# f103ret6_w25q64_20200910.net
KiCad netlist of a schematic drawn in Altium Designer
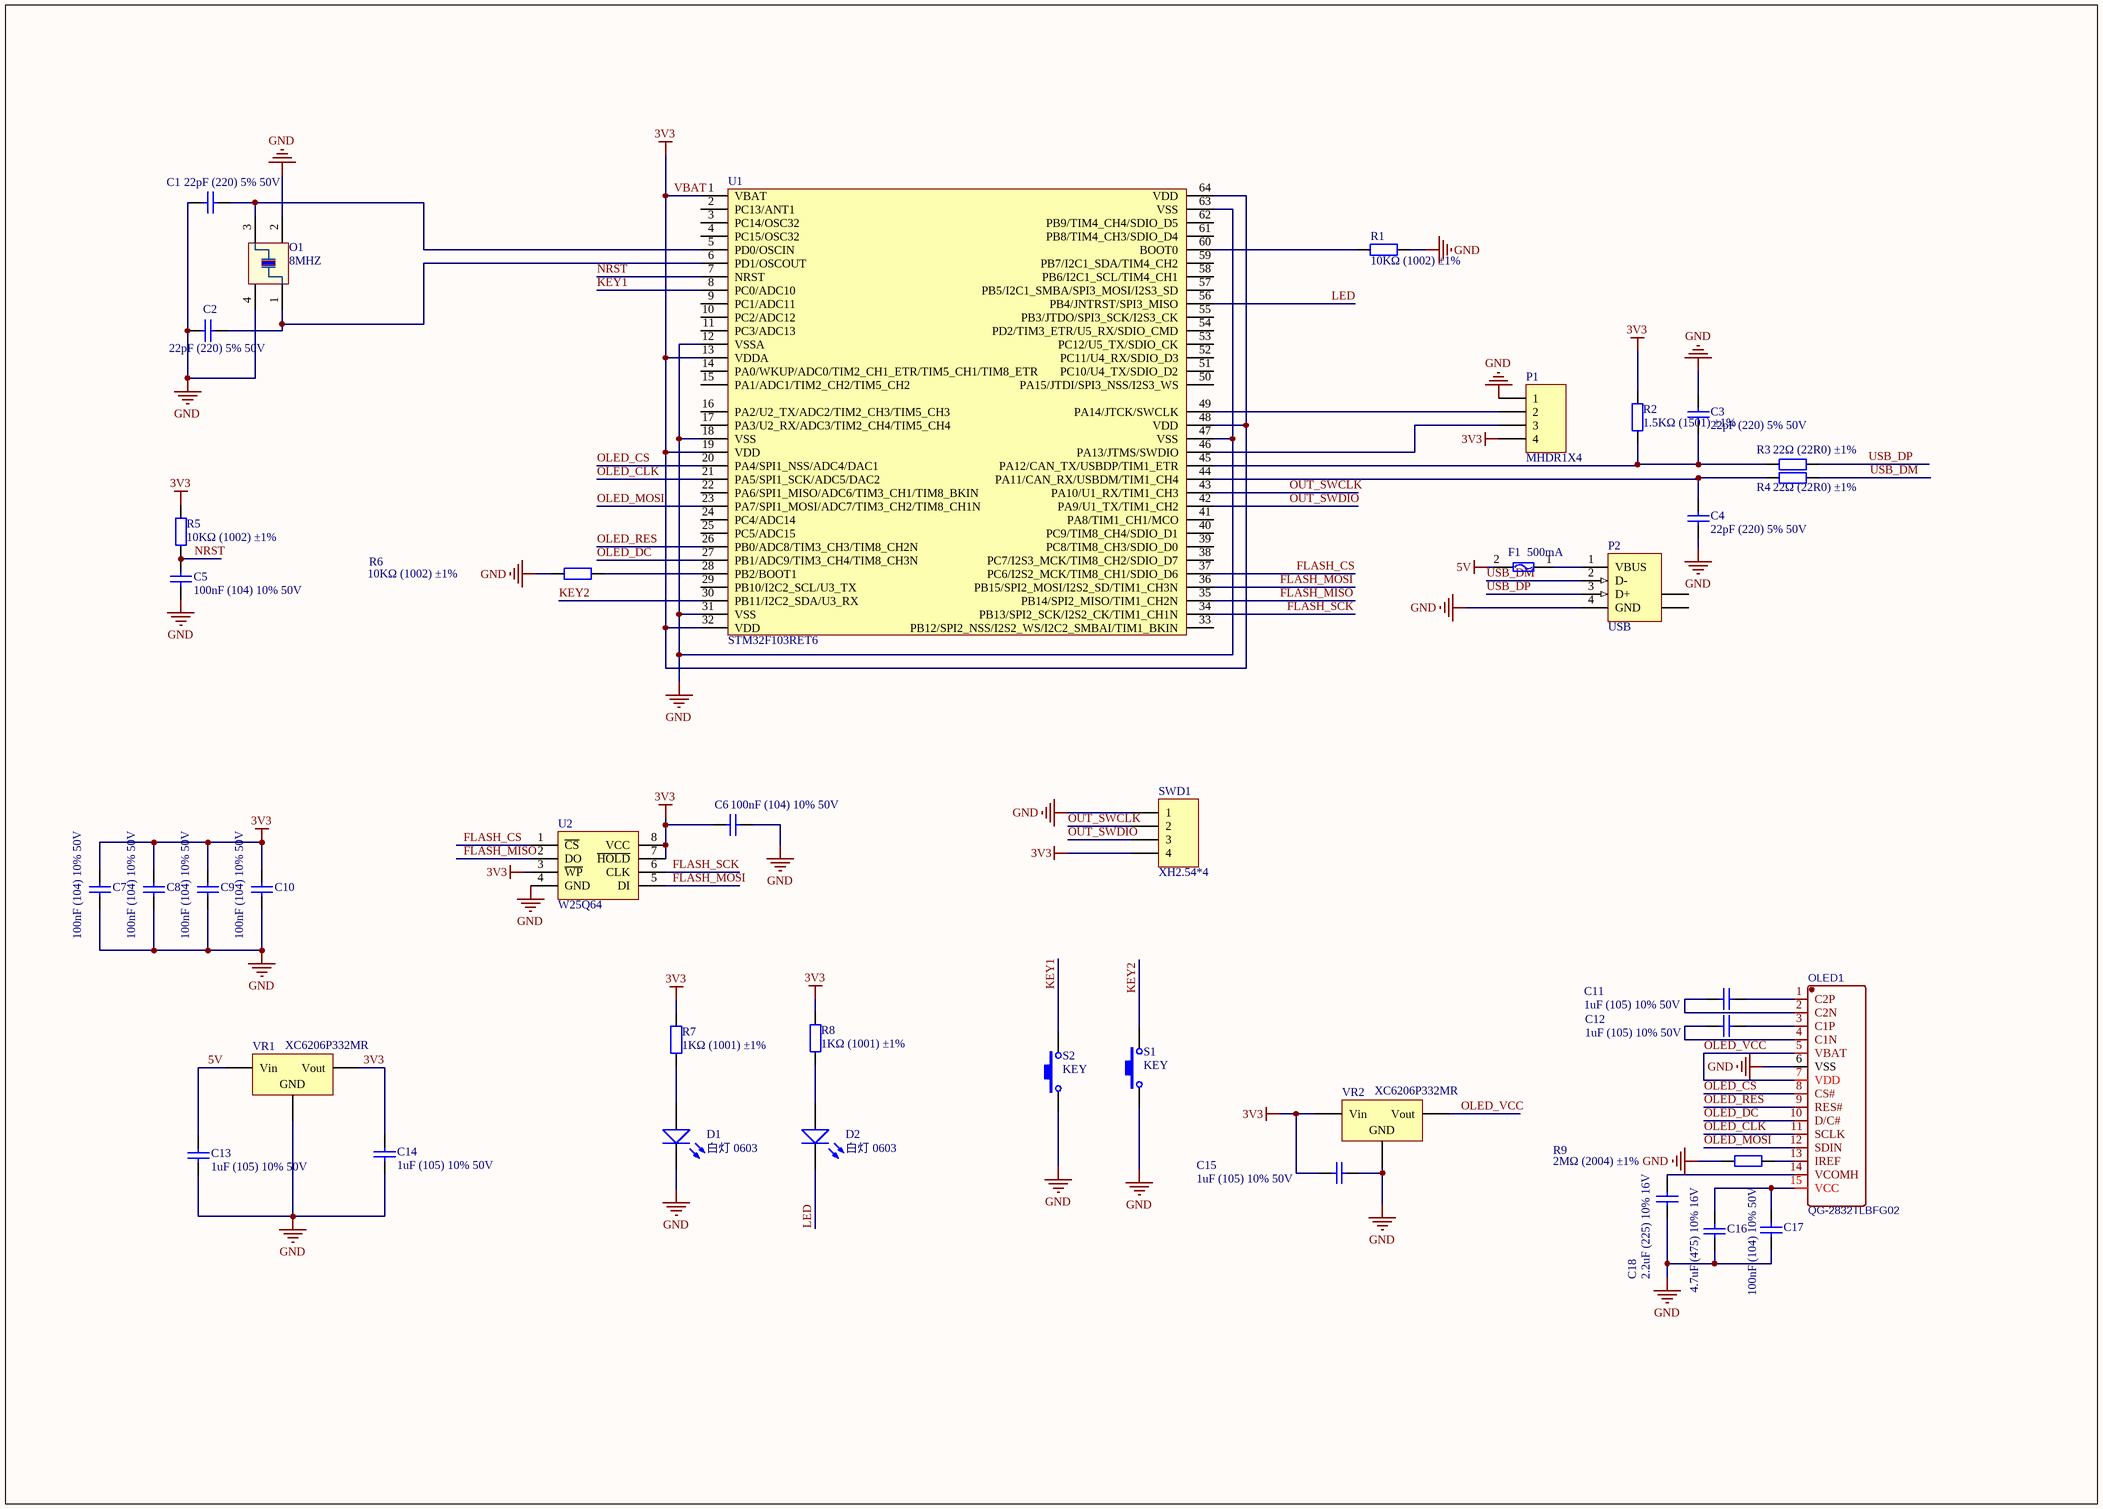
[diagram p0: f103ret6_w25q64_20200910.SchDoc]

(export (version "E")
  (design (tool "Eeschema 10.0.6"))
  (components
    (comp (ref "C1")
      (value "22pF (220) 5% 50V")
      (footprint "0603_C")
      (description "贴片电容")
      (libsource (lib "Miscellaneous Devices LC") (part "0603 22pF (220) 5% 50V"))
    )
    (comp (ref "C2")
      (value "22pF (220) 5% 50V")
      (footprint "0603_C")
      (description "贴片电容")
      (libsource (lib "Miscellaneous Devices LC") (part "0603 22pF (220) 5% 50V"))
    )
    (comp (ref "C3")
      (value "22pF (220) 5% 50V")
      (footprint "0603_C")
      (description "贴片电容")
      (libsource (lib "Miscellaneous Devices LC") (part "0603 22pF (220) 5% 50V"))
    )
    (comp (ref "C4")
      (value "22pF (220) 5% 50V")
      (footprint "0603_C")
      (description "贴片电容")
      (libsource (lib "Miscellaneous Devices LC") (part "0603 22pF (220) 5% 50V"))
    )
    (comp (ref "C5")
      (value "100nF (104) 10% 50V")
      (footprint "0603_C")
      (description "贴片电容")
      (libsource (lib "Miscellaneous Devices LC") (part "0603 100nF (104) 10% 50V"))
    )
    (comp (ref "C6")
      (value "100nF (104) 10% 50V")
      (footprint "0603_C")
      (description "贴片电容")
      (libsource (lib "Miscellaneous Devices LC") (part "0603 100nF (104) 10% 50V"))
    )
    (comp (ref "C7")
      (value "100nF (104) 10% 50V")
      (footprint "0603_C")
      (description "贴片电容")
      (libsource (lib "Miscellaneous Devices LC") (part "0603 100nF (104) 10% 50V"))
    )
    (comp (ref "C8")
      (value "100nF (104) 10% 50V")
      (footprint "0603_C")
      (description "贴片电容")
      (libsource (lib "Miscellaneous Devices LC") (part "0603 100nF (104) 10% 50V"))
    )
    (comp (ref "C9")
      (value "100nF (104) 10% 50V")
      (footprint "0603_C")
      (description "贴片电容")
      (libsource (lib "Miscellaneous Devices LC") (part "0603 100nF (104) 10% 50V"))
    )
    (comp (ref "C10")
      (value "100nF (104) 10% 50V")
      (footprint "0603_C")
      (description "贴片电容")
      (libsource (lib "Miscellaneous Devices LC") (part "0603 100nF (104) 10% 50V"))
    )
    (comp (ref "C11")
      (value "1uF (105) 10% 50V")
      (footprint "0603_C")
      (description "贴片电容")
      (libsource (lib "Miscellaneous Devices LC") (part "0603 1uF (105) 10% 50V"))
    )
    (comp (ref "C12")
      (value "1uF (105) 10% 50V")
      (footprint "0603_C")
      (description "贴片电容")
      (libsource (lib "Miscellaneous Devices LC") (part "0603 1uF (105) 10% 50V"))
    )
    (comp (ref "C13")
      (value "1uF (105) 10% 50V")
      (footprint "0603_C")
      (description "贴片电容")
      (libsource (lib "Miscellaneous Devices LC") (part "0603 1uF (105) 10% 50V"))
    )
    (comp (ref "C14")
      (value "1uF (105) 10% 50V")
      (footprint "0603_C")
      (description "贴片电容")
      (libsource (lib "Miscellaneous Devices LC") (part "0603 1uF (105) 10% 50V"))
    )
    (comp (ref "C15")
      (value "1uF (105) 10% 50V")
      (footprint "0603_C")
      (description "贴片电容")
      (libsource (lib "Miscellaneous Devices LC") (part "0603 1uF (105) 10% 50V"))
    )
    (comp (ref "C16")
      (value "4.7uF (475) 10% 16V")
      (footprint "0603_C")
      (description "贴片电容")
      (libsource (lib "Miscellaneous Devices LC") (part "0603 4.7uF (475) 10% 16V"))
    )
    (comp (ref "C17")
      (value "100nF (104) 10% 50V")
      (footprint "0603_C")
      (description "贴片电容")
      (libsource (lib "Miscellaneous Devices LC") (part "0603 100nF (104) 10% 50V"))
    )
    (comp (ref "C18")
      (value "2.2uF (225) 10% 16V")
      (footprint "0603_C")
      (description "贴片电容")
      (libsource (lib "Miscellaneous Devices LC") (part "0603 2.2uF (225) 10% 16V"))
    )
    (comp (ref "D1")
      (value "白灯 0603")
      (footprint "0603_LED_S1")
      (description "发光二极管")
      (libsource (lib "Miscellaneous Devices LC") (part "0603 白灯"))
    )
    (comp (ref "D2")
      (value "白灯 0603")
      (footprint "0603_LED_S1")
      (description "发光二极管")
      (libsource (lib "Miscellaneous Devices LC") (part "0603 白灯"))
    )
    (comp (ref "F1")
      (value "500mA")
      (footprint "0805")
      (description "保险丝，熔断丝")
      (libsource (lib "Free Documents") (part "FUSE"))
    )
    (comp (ref "O1")
      (value "8MHZ")
      (footprint "f103ret6_w25q64_20200910:3225")
      (description "OSC")
      (libsource (lib "altium-import") (part "root_1_OSC_"))
    )
    (comp (ref "OLED1")
      (value "QG-2832TLBFG02")
      (footprint "0.91-OLED")
      (fields (field (name "BOM_SUPPLIER PART") "C91220") (field (name "CONTRIBUTOR") "LCSC"))
      (libsource (lib "0.91-oled") (part "0.91-OLED"))
    )
    (comp (ref "P1")
      (value "MHDR1X4")
      (footprint "MHDR1X4")
      (description "Header, 4-Pin")
      (fields (field (name "PUBLISHER") "Altium Limited"))
      (libsource (lib "Miscellaneous Connectors") (part "MHDR1X4"))
    )
    (comp (ref "P2")
      (value "USB")
      (footprint "USB_A/P_B")
      (description "USB 1.1, Right Angle, SMT, A Type, Plug, 4 Position, Natural")
      (fields (field (name "PUBLISHER") "Altium Limited"))
      (libsource (lib "AMP Serial Bus USB") (part "1470695-2"))
    )
    (comp (ref "R1")
      (value "10KΩ (1002) ±1%")
      (footprint "0603_R")
      (description "贴片电阻")
      (libsource (lib "") (part "0603 10KΩ (1002) 1%_1"))
    )
    (comp (ref "R2")
      (value "1.5KΩ (1501) ±1%")
      (footprint "0603_R")
      (description "贴片电阻")
      (libsource (lib "Miscellaneous Devices LC") (part "0603 1.5KΩ (1501) 1%"))
    )
    (comp (ref "R3")
      (value "22Ω (22R0) ±1%")
      (footprint "0603_R")
      (description "贴片电阻")
      (libsource (lib "Miscellaneous Devices LC") (part "0603 22Ω (22R0) 1%"))
    )
    (comp (ref "R4")
      (value "22Ω (22R0) ±1%")
      (footprint "0603_R")
      (description "贴片电阻")
      (libsource (lib "Miscellaneous Devices LC") (part "0603 22Ω (22R0) 1%"))
    )
    (comp (ref "R5")
      (value "10KΩ (1002) ±1%")
      (footprint "0603_R")
      (description "贴片电阻")
      (libsource (lib "Miscellaneous Devices LC") (part "0603 10KΩ (1002) 1%"))
    )
    (comp (ref "R6")
      (value "10KΩ (1002) ±1%")
      (footprint "0603_R")
      (description "贴片电阻")
      (libsource (lib "") (part "0603 10KΩ (1002) 1%_2"))
    )
    (comp (ref "R7")
      (value "1KΩ (1001) ±1%")
      (footprint "0603_R")
      (description "贴片电阻")
      (libsource (lib "Miscellaneous Devices LC") (part "0603 1KΩ (1001) 1%"))
    )
    (comp (ref "R8")
      (value "1KΩ (1001) ±1%")
      (footprint "0603_R")
      (description "贴片电阻")
      (libsource (lib "Miscellaneous Devices LC") (part "0603 1KΩ (1001) 1%"))
    )
    (comp (ref "R9")
      (value "2MΩ (2004) ±1%")
      (footprint "0603_R")
      (description "贴片电阻")
      (libsource (lib "Miscellaneous Devices LC") (part "0603 2MΩ (2004) 1%"))
    )
    (comp (ref "S1") (value "KEY") (footprint "KEY") (libsource (lib "altium-import") (part "root_1_KEY_")))
    (comp (ref "S2") (value "KEY") (footprint "KEY") (libsource (lib "altium-import") (part "root_1_KEY_")))
    (comp (ref "SWD1")
      (value "XH2.54*4")
      (footprint "XH2.54-WI-4P")
      (description "Header, 4-Pin")
      (fields (field (name "PUBLISHER") "Altium Limited"))
      (libsource (lib "Mogoo-GM_B1-PLCPCB-V1.0") (part "Header 4"))
    )
    (comp (ref "U1")
      (value "STM32F103RET6")
      (footprint "f103ret6_w25q64_20200910:LQFP64")
      (description "STM32F103RxT6")
      (libsource (lib "Free Documents") (part "STM32F103RxT6"))
    )
    (comp (ref "U2")
      (value "W25Q64")
      (footprint "f103ret6_w25q64_20200910:SOP8_W")
      (description "W25Q")
      (libsource (lib "Free Documents") (part "W25Q"))
    )
    (comp (ref "VR1")
      (value "XC6206P332MR")
      (footprint "SOT-23-3L")
      (description "低压差线性稳压(LDO)")
      (libsource (lib "Miscellaneous Devices LC") (part "SOT-23 XC6206P332MR"))
    )
    (comp (ref "VR2")
      (value "XC6206P332MR")
      (footprint "SOT-23-3L")
      (description "低压差线性稳压(LDO)")
      (libsource (lib "Miscellaneous Devices LC") (part "SOT-23 XC6206P332MR"))
    )
  )
  (nets
    (net (code "1") (name "/FLASH_CS") (class "Default")
      (node (ref "U1") (pin "37") (pinfunction "PC6/I2S2_MCK/TIM8_CH1/SDIO_D6_37") (pintype "passive"))
      (node (ref "U2") (pin "1") (pinfunction "~{CS}_1") (pintype "passive"))
    )
    (net (code "2") (name "/FLASH_MISO") (class "Default")
      (node (ref "U1") (pin "35") (pinfunction "PB14/SPI2_MISO/TIM1_CH2N_35") (pintype "passive"))
      (node (ref "U2") (pin "2") (pinfunction "DO_2") (pintype "passive"))
    )
    (net (code "3") (name "/FLASH_MOSI") (class "Default")
      (node (ref "U1") (pin "36") (pinfunction "PB15/SPI2_MOSI/I2S2_SD/TIM1_CH3N_36") (pintype "passive"))
      (node (ref "U2") (pin "5") (pinfunction "DI_5") (pintype "passive"))
    )
    (net (code "4") (name "/FLASH_SCK") (class "Default")
      (node (ref "U1") (pin "34") (pinfunction "PB13/SPI2_SCK/I2S2_CK/TIM1_CH1N_34") (pintype "passive"))
      (node (ref "U2") (pin "6") (pinfunction "CLK_6") (pintype "passive"))
    )
    (net (code "5") (name "/KEY1") (class "Default")
      (node (ref "S2") (pin "2") (pinfunction "2_2") (pintype "power_in"))
      (node (ref "U1") (pin "8") (pinfunction "PC0/ADC10_8") (pintype "passive"))
    )
    (net (code "6") (name "/KEY2") (class "Default")
      (node (ref "S1") (pin "2") (pinfunction "2_2") (pintype "power_in"))
      (node (ref "U1") (pin "30") (pinfunction "PB11/I2C2_SDA/U3_RX_30") (pintype "passive"))
    )
    (net (code "7") (name "/LED") (class "Default")
      (node (ref "D2") (pin "K") (pinfunction "K_K") (pintype "passive"))
      (node (ref "U1") (pin "56") (pinfunction "PB4/JNTRST/SPI3_MISO_56") (pintype "passive"))
    )
    (net (code "8") (name "/NRST") (class "Default")
      (node (ref "C5") (pin "2") (pinfunction "2_2") (pintype "passive"))
      (node (ref "R5") (pin "1") (pinfunction "1_1") (pintype "passive"))
      (node (ref "U1") (pin "7") (pinfunction "NRST_7") (pintype "passive"))
    )
    (net (code "9") (name "/OLED_CLK") (class "Default")
      (node (ref "OLED1") (pin "11") (pinfunction "SCLK_11") (pintype "passive"))
      (node (ref "U1") (pin "21") (pinfunction "PA5/SPI1_SCK/ADC5/DAC2_21") (pintype "passive"))
    )
    (net (code "10") (name "/OLED_CS") (class "Default")
      (node (ref "OLED1") (pin "8") (pinfunction "CS#_8") (pintype "passive"))
      (node (ref "U1") (pin "20") (pinfunction "PA4/SPI1_NSS/ADC4/DAC1_20") (pintype "passive"))
    )
    (net (code "11") (name "/OLED_DC") (class "Default")
      (node (ref "OLED1") (pin "10") (pinfunction "D/C#_10") (pintype "passive"))
      (node (ref "U1") (pin "27") (pinfunction "PB1/ADC9/TIM3_CH4/TIM8_CH3N_27") (pintype "passive"))
    )
    (net (code "12") (name "/OLED_MOSI") (class "Default")
      (node (ref "OLED1") (pin "12") (pinfunction "SDIN_12") (pintype "passive"))
      (node (ref "U1") (pin "23") (pinfunction "PA7/SPI1_MOSI/ADC7/TIM3_CH2/TIM8_CH1N_23") (pintype "passive"))
    )
    (net (code "13") (name "/OLED_RES") (class "Default")
      (node (ref "OLED1") (pin "9") (pinfunction "RES#_9") (pintype "passive"))
      (node (ref "U1") (pin "26") (pinfunction "PB0/ADC8/TIM3_CH3/TIM8_CH2N_26") (pintype "passive"))
    )
    (net (code "14") (name "/OLED_VCC") (class "Default")
      (node (ref "OLED1") (pin "5") (pinfunction "VBAT_5") (pintype "passive"))
      (node (ref "OLED1") (pin "7") (pinfunction "VDD_7") (pintype "passive"))
      (node (ref "VR2") (pin "2") (pinfunction "Vout_2") (pintype "passive"))
    )
    (net (code "15") (name "/OUT_SWCLK") (class "Default")
      (node (ref "SWD1") (pin "2") (pinfunction "2_2") (pintype "passive"))
      (node (ref "U1") (pin "43") (pinfunction "PA10/U1_RX/TIM1_CH3_43") (pintype "passive"))
    )
    (net (code "16") (name "/OUT_SWDIO") (class "Default")
      (node (ref "SWD1") (pin "3") (pinfunction "3_3") (pintype "passive"))
      (node (ref "U1") (pin "42") (pinfunction "PA9/U1_TX/TIM1_CH2_42") (pintype "passive"))
    )
    (net (code "17") (name "/USB_DM") (class "Default")
      (node (ref "P2") (pin "2") (pinfunction "D-_2") (pintype "input"))
      (node (ref "R4") (pin "2") (pinfunction "2_2") (pintype "passive"))
    )
    (net (code "18") (name "/USB_DP") (class "Default")
      (node (ref "P2") (pin "3") (pinfunction "D+_3") (pintype "input"))
      (node (ref "R3") (pin "2") (pinfunction "2_2") (pintype "passive"))
    )
    (net (code "19") (name "3V3") (class "Default")
      (node (ref "C10") (pin "2") (pinfunction "2_2") (pintype "passive"))
      (node (ref "C14") (pin "2") (pinfunction "2_2") (pintype "passive"))
      (node (ref "C15") (pin "1") (pinfunction "1_1") (pintype "passive"))
      (node (ref "C6") (pin "1") (pinfunction "1_1") (pintype "passive"))
      (node (ref "C7") (pin "2") (pinfunction "2_2") (pintype "passive"))
      (node (ref "C8") (pin "2") (pinfunction "2_2") (pintype "passive"))
      (node (ref "C9") (pin "2") (pinfunction "2_2") (pintype "passive"))
      (node (ref "P1") (pin "4") (pinfunction "4_4") (pintype "passive"))
      (node (ref "R2") (pin "1") (pinfunction "1_1") (pintype "passive"))
      (node (ref "R5") (pin "2") (pinfunction "2_2") (pintype "passive"))
      (node (ref "R7") (pin "2") (pinfunction "2_2") (pintype "passive"))
      (node (ref "R8") (pin "2") (pinfunction "2_2") (pintype "passive"))
      (node (ref "SWD1") (pin "4") (pinfunction "4_4") (pintype "passive"))
      (node (ref "U1") (pin "1") (pinfunction "VBAT_1") (pintype "passive"))
      (node (ref "U1") (pin "13") (pinfunction "VDDA_13") (pintype "passive"))
      (node (ref "U1") (pin "19") (pinfunction "VDD_19") (pintype "passive"))
      (node (ref "U1") (pin "32") (pinfunction "VDD_32") (pintype "passive"))
      (node (ref "U1") (pin "48") (pinfunction "VDD_48") (pintype "passive"))
      (node (ref "U1") (pin "64") (pinfunction "VDD_64") (pintype "passive"))
      (node (ref "U2") (pin "3") (pinfunction "~{WP}_3") (pintype "passive"))
      (node (ref "U2") (pin "7") (pinfunction "~{HOLD}_7") (pintype "passive"))
      (node (ref "U2") (pin "8") (pinfunction "VCC_8") (pintype "passive"))
      (node (ref "VR1") (pin "2") (pinfunction "Vout_2") (pintype "passive"))
      (node (ref "VR2") (pin "3") (pinfunction "Vin_3") (pintype "passive"))
    )
    (net (code "20") (name "5V") (class "Default")
      (node (ref "C13") (pin "2") (pinfunction "2_2") (pintype "passive"))
      (node (ref "F1") (pin "2") (pinfunction "5_2") (pintype "passive"))
      (node (ref "VR1") (pin "3") (pinfunction "Vin_3") (pintype "passive"))
    )
    (net (code "21") (name "GND") (class "Default")
      (node (ref "C1") (pin "2") (pinfunction "2_2") (pintype "passive"))
      (node (ref "C10") (pin "1") (pinfunction "1_1") (pintype "passive"))
      (node (ref "C13") (pin "1") (pinfunction "1_1") (pintype "passive"))
      (node (ref "C14") (pin "1") (pinfunction "1_1") (pintype "passive"))
      (node (ref "C15") (pin "2") (pinfunction "2_2") (pintype "passive"))
      (node (ref "C16") (pin "1") (pinfunction "1_1") (pintype "passive"))
      (node (ref "C17") (pin "1") (pinfunction "1_1") (pintype "passive"))
      (node (ref "C18") (pin "1") (pinfunction "1_1") (pintype "passive"))
      (node (ref "C2") (pin "2") (pinfunction "2_2") (pintype "passive"))
      (node (ref "C3") (pin "2") (pinfunction "2_2") (pintype "passive"))
      (node (ref "C4") (pin "1") (pinfunction "1_1") (pintype "passive"))
      (node (ref "C5") (pin "1") (pinfunction "1_1") (pintype "passive"))
      (node (ref "C6") (pin "2") (pinfunction "2_2") (pintype "passive"))
      (node (ref "C7") (pin "1") (pinfunction "1_1") (pintype "passive"))
      (node (ref "C8") (pin "1") (pinfunction "1_1") (pintype "passive"))
      (node (ref "C9") (pin "1") (pinfunction "1_1") (pintype "passive"))
      (node (ref "D1") (pin "K") (pinfunction "K_K") (pintype "passive"))
      (node (ref "O1") (pin "2") (pintype "passive"))
      (node (ref "O1") (pin "4") (pintype "passive"))
      (node (ref "OLED1") (pin "6") (pinfunction "VSS_6") (pintype "passive"))
      (node (ref "P1") (pin "1") (pinfunction "1_1") (pintype "passive"))
      (node (ref "P2") (pin "4") (pinfunction "GND_4") (pintype "power_in"))
      (node (ref "R1") (pin "1") (pinfunction "1_1") (pintype "passive"))
      (node (ref "R6") (pin "1") (pinfunction "1_1") (pintype "passive"))
      (node (ref "R9") (pin "1") (pinfunction "1_1") (pintype "passive"))
      (node (ref "S1") (pin "1") (pinfunction "1_1") (pintype "power_in"))
      (node (ref "S2") (pin "1") (pinfunction "1_1") (pintype "power_in"))
      (node (ref "SWD1") (pin "1") (pinfunction "1_1") (pintype "passive"))
      (node (ref "U1") (pin "12") (pinfunction "VSSA_12") (pintype "passive"))
      (node (ref "U1") (pin "18") (pinfunction "VSS_18") (pintype "passive"))
      (node (ref "U1") (pin "31") (pinfunction "VSS_31") (pintype "passive"))
      (node (ref "U1") (pin "47") (pinfunction "VSS_47") (pintype "passive"))
      (node (ref "U1") (pin "63") (pinfunction "VSS_63") (pintype "passive"))
      (node (ref "U2") (pin "4") (pinfunction "GND_4") (pintype "passive"))
      (node (ref "VR1") (pin "1") (pinfunction "GND_1") (pintype "passive"))
      (node (ref "VR2") (pin "1") (pinfunction "GND_1") (pintype "passive"))
    )
    (net (code "22") (name "Net-(D1-PadA)") (class "Default")
      (node (ref "D1") (pin "A") (pinfunction "A_A") (pintype "passive"))
      (node (ref "R7") (pin "1") (pinfunction "1_1") (pintype "passive"))
    )
    (net (code "23") (name "Net-(D2-PadA)") (class "Default")
      (node (ref "D2") (pin "A") (pinfunction "A_A") (pintype "passive"))
      (node (ref "R8") (pin "1") (pinfunction "1_1") (pintype "passive"))
    )
    (net (code "24") (name "Net-(F1-4)") (class "Default")
      (node (ref "F1") (pin "1") (pinfunction "4_1") (pintype "passive"))
      (node (ref "P2") (pin "1") (pinfunction "VBUS_1") (pintype "power_in"))
    )
    (net (code "25") (name "Net-(OLED1-C1N)") (class "Default")
      (node (ref "C12") (pin "1") (pinfunction "1_1") (pintype "passive"))
      (node (ref "OLED1") (pin "4") (pinfunction "C1N_4") (pintype "passive"))
    )
    (net (code "26") (name "Net-(OLED1-C1P)") (class "Default")
      (node (ref "C12") (pin "2") (pinfunction "2_2") (pintype "passive"))
      (node (ref "OLED1") (pin "3") (pinfunction "C1P_3") (pintype "passive"))
    )
    (net (code "27") (name "Net-(OLED1-C2N)") (class "Default")
      (node (ref "C11") (pin "1") (pinfunction "1_1") (pintype "passive"))
      (node (ref "OLED1") (pin "2") (pinfunction "C2N_2") (pintype "passive"))
    )
    (net (code "28") (name "Net-(OLED1-C2P)") (class "Default")
      (node (ref "C11") (pin "2") (pinfunction "2_2") (pintype "passive"))
      (node (ref "OLED1") (pin "1") (pinfunction "C2P_1") (pintype "passive"))
    )
    (net (code "29") (name "Net-(OLED1-IREF)") (class "Default")
      (node (ref "OLED1") (pin "13") (pinfunction "IREF_13") (pintype "passive"))
      (node (ref "R9") (pin "2") (pinfunction "2_2") (pintype "passive"))
    )
    (net (code "30") (name "Net-(OLED1-VCC)") (class "Default")
      (node (ref "C16") (pin "2") (pinfunction "2_2") (pintype "passive"))
      (node (ref "C17") (pin "2") (pinfunction "2_2") (pintype "passive"))
      (node (ref "OLED1") (pin "15") (pinfunction "VCC_15") (pintype "passive"))
    )
    (net (code "31") (name "Net-(OLED1-VCOMH)") (class "Default")
      (node (ref "C18") (pin "2") (pinfunction "2_2") (pintype "passive"))
      (node (ref "OLED1") (pin "14") (pinfunction "VCOMH_14") (pintype "passive"))
    )
    (net (code "32") (name "Net-(U1-BOOT0)") (class "Default")
      (node (ref "R1") (pin "2") (pinfunction "2_2") (pintype "passive"))
      (node (ref "U1") (pin "60") (pinfunction "BOOT0_60") (pintype "passive"))
    )
    (net (code "33") (name "Net-(U1-PA11{slash}CAN_RX{slash}USBDM{slash}TIM1_CH4)") (class "Default")
      (node (ref "C4") (pin "2") (pinfunction "2_2") (pintype "passive"))
      (node (ref "R4") (pin "1") (pinfunction "1_1") (pintype "passive"))
      (node (ref "U1") (pin "44") (pinfunction "PA11/CAN_RX/USBDM/TIM1_CH4_44") (pintype "passive"))
    )
    (net (code "34") (name "Net-(U1-PA12{slash}CAN_TX{slash}USBDP{slash}TIM1_ETR)") (class "Default")
      (node (ref "C3") (pin "1") (pinfunction "1_1") (pintype "passive"))
      (node (ref "R2") (pin "2") (pinfunction "2_2") (pintype "passive"))
      (node (ref "R3") (pin "1") (pinfunction "1_1") (pintype "passive"))
      (node (ref "U1") (pin "45") (pinfunction "PA12/CAN_TX/USBDP/TIM1_ETR_45") (pintype "passive"))
    )
    (net (code "35") (name "Net-(U1-PA13{slash}JTMS{slash}SWDIO)") (class "Default")
      (node (ref "P1") (pin "3") (pinfunction "3_3") (pintype "passive"))
      (node (ref "U1") (pin "46") (pinfunction "PA13/JTMS/SWDIO_46") (pintype "passive"))
    )
    (net (code "36") (name "Net-(U1-PA14{slash}JTCK{slash}SWCLK)") (class "Default")
      (node (ref "P1") (pin "2") (pinfunction "2_2") (pintype "passive"))
      (node (ref "U1") (pin "49") (pinfunction "PA14/JTCK/SWCLK_49") (pintype "passive"))
    )
    (net (code "37") (name "Net-(U1-PB2{slash}BOOT1)") (class "Default")
      (node (ref "R6") (pin "2") (pinfunction "2_2") (pintype "passive"))
      (node (ref "U1") (pin "28") (pinfunction "PB2/BOOT1_28") (pintype "passive"))
    )
    (net (code "38") (name "Net-(U1-PD0{slash}OSCIN)") (class "Default")
      (node (ref "C1") (pin "1") (pinfunction "1_1") (pintype "passive"))
      (node (ref "O1") (pin "3") (pintype "passive"))
      (node (ref "U1") (pin "5") (pinfunction "PD0/OSCIN_5") (pintype "passive"))
    )
    (net (code "39") (name "Net-(U1-PD1{slash}OSCOUT)") (class "Default")
      (node (ref "C2") (pin "1") (pinfunction "1_1") (pintype "passive"))
      (node (ref "O1") (pin "1") (pintype "passive"))
      (node (ref "U1") (pin "6") (pinfunction "PD1/OSCOUT_6") (pintype "passive"))
    )
    (net (code "40") (name "unconnected-(P2-SHLD-Pad5)") (class "Default")
      (node (ref "P2") (pin "5") (pinfunction "SHLD_5") (pintype "passive"))
    )
    (net (code "41") (name "unconnected-(P2-SHLD-Pad6)") (class "Default")
      (node (ref "P2") (pin "6") (pinfunction "SHLD_6") (pintype "passive"))
    )
    (net (code "42") (name "unconnected-(U1-PA0{slash}WKUP{slash}ADC0{slash}TIM2_CH1_ETR{slash}TIM5_CH1{slash}TIM8_ETR-Pad14)") (class "Default")
      (node (ref "U1") (pin "14") (pinfunction "PA0/WKUP/ADC0/TIM2_CH1_ETR/TIM5_CH1/TIM8_ETR_14") (pintype "passive"))
    )
    (net (code "43") (name "unconnected-(U1-PA1{slash}ADC1{slash}TIM2_CH2{slash}TIM5_CH2-Pad15)") (class "Default")
      (node (ref "U1") (pin "15") (pinfunction "PA1/ADC1/TIM2_CH2/TIM5_CH2_15") (pintype "passive"))
    )
    (net (code "44") (name "unconnected-(U1-PA2{slash}U2_TX{slash}ADC2{slash}TIM2_CH3{slash}TIM5_CH3-Pad16)") (class "Default")
      (node (ref "U1") (pin "16") (pinfunction "PA2/U2_TX/ADC2/TIM2_CH3/TIM5_CH3_16") (pintype "passive"))
    )
    (net (code "45") (name "unconnected-(U1-PA3{slash}U2_RX{slash}ADC3{slash}TIM2_CH4{slash}TIM5_CH4-Pad17)") (class "Default")
      (node (ref "U1") (pin "17") (pinfunction "PA3/U2_RX/ADC3/TIM2_CH4/TIM5_CH4_17") (pintype "passive"))
    )
    (net (code "46") (name "unconnected-(U1-PA6{slash}SPI1_MISO{slash}ADC6{slash}TIM3_CH1{slash}TIM8_BKIN-Pad22)") (class "Default")
      (node (ref "U1") (pin "22") (pinfunction "PA6/SPI1_MISO/ADC6/TIM3_CH1/TIM8_BKIN_22") (pintype "passive"))
    )
    (net (code "47") (name "unconnected-(U1-PA8{slash}TIM1_CH1{slash}MCO-Pad41)") (class "Default")
      (node (ref "U1") (pin "41") (pinfunction "PA8/TIM1_CH1/MCO_41") (pintype "passive"))
    )
    (net (code "48") (name "unconnected-(U1-PA15{slash}JTDI{slash}SPI3_NSS{slash}I2S3_WS-Pad50)") (class "Default")
      (node (ref "U1") (pin "50") (pinfunction "PA15/JTDI/SPI3_NSS/I2S3_WS_50") (pintype "passive"))
    )
    (net (code "49") (name "unconnected-(U1-PB3{slash}JTDO{slash}SPI3_SCK{slash}I2S3_CK-Pad55)") (class "Default")
      (node (ref "U1") (pin "55") (pinfunction "PB3/JTDO/SPI3_SCK/I2S3_CK_55") (pintype "passive"))
    )
    (net (code "50") (name "unconnected-(U1-PB5{slash}I2C1_SMBA{slash}SPI3_MOSI{slash}I2S3_SD-Pad57)") (class "Default")
      (node (ref "U1") (pin "57") (pinfunction "PB5/I2C1_SMBA/SPI3_MOSI/I2S3_SD_57") (pintype "passive"))
    )
    (net (code "51") (name "unconnected-(U1-PB6{slash}I2C1_SCL{slash}TIM4_CH1-Pad58)") (class "Default")
      (node (ref "U1") (pin "58") (pinfunction "PB6/I2C1_SCL/TIM4_CH1_58") (pintype "passive"))
    )
    (net (code "52") (name "unconnected-(U1-PB7{slash}I2C1_SDA{slash}TIM4_CH2-Pad59)") (class "Default")
      (node (ref "U1") (pin "59") (pinfunction "PB7/I2C1_SDA/TIM4_CH2_59") (pintype "passive"))
    )
    (net (code "53") (name "unconnected-(U1-PB8{slash}TIM4_CH3{slash}SDIO_D4-Pad61)") (class "Default")
      (node (ref "U1") (pin "61") (pinfunction "PB8/TIM4_CH3/SDIO_D4_61") (pintype "passive"))
    )
    (net (code "54") (name "unconnected-(U1-PB9{slash}TIM4_CH4{slash}SDIO_D5-Pad62)") (class "Default")
      (node (ref "U1") (pin "62") (pinfunction "PB9/TIM4_CH4/SDIO_D5_62") (pintype "passive"))
    )
    (net (code "55") (name "unconnected-(U1-PB10{slash}I2C2_SCL{slash}U3_TX-Pad29)") (class "Default")
      (node (ref "U1") (pin "29") (pinfunction "PB10/I2C2_SCL/U3_TX_29") (pintype "passive"))
    )
    (net (code "56") (name "unconnected-(U1-PB12{slash}SPI2_NSS{slash}I2S2_WS{slash}I2C2_SMBAI{slash}TIM1_BKIN-Pad33)") (class "Default")
      (node (ref "U1") (pin "33") (pinfunction "PB12/SPI2_NSS/I2S2_WS/I2C2_SMBAI/TIM1_BKIN_33") (pintype "passive"))
    )
    (net (code "57") (name "unconnected-(U1-PC1{slash}ADC11-Pad9)") (class "Default")
      (node (ref "U1") (pin "9") (pinfunction "PC1/ADC11_9") (pintype "passive"))
    )
    (net (code "58") (name "unconnected-(U1-PC2{slash}ADC12-Pad10)") (class "Default")
      (node (ref "U1") (pin "10") (pinfunction "PC2/ADC12_10") (pintype "passive"))
    )
    (net (code "59") (name "unconnected-(U1-PC3{slash}ADC13-Pad11)") (class "Default")
      (node (ref "U1") (pin "11") (pinfunction "PC3/ADC13_11") (pintype "passive"))
    )
    (net (code "60") (name "unconnected-(U1-PC4{slash}ADC14-Pad24)") (class "Default")
      (node (ref "U1") (pin "24") (pinfunction "PC4/ADC14_24") (pintype "passive"))
    )
    (net (code "61") (name "unconnected-(U1-PC5{slash}ADC15-Pad25)") (class "Default")
      (node (ref "U1") (pin "25") (pinfunction "PC5/ADC15_25") (pintype "passive"))
    )
    (net (code "62") (name "unconnected-(U1-PC7{slash}I2S3_MCK{slash}TIM8_CH2{slash}SDIO_D7-Pad38)") (class "Default")
      (node (ref "U1") (pin "38") (pinfunction "PC7/I2S3_MCK/TIM8_CH2/SDIO_D7_38") (pintype "passive"))
    )
    (net (code "63") (name "unconnected-(U1-PC8{slash}TIM8_CH3{slash}SDIO_D0-Pad39)") (class "Default")
      (node (ref "U1") (pin "39") (pinfunction "PC8/TIM8_CH3/SDIO_D0_39") (pintype "passive"))
    )
    (net (code "64") (name "unconnected-(U1-PC9{slash}TIM8_CH4{slash}SDIO_D1-Pad40)") (class "Default")
      (node (ref "U1") (pin "40") (pinfunction "PC9/TIM8_CH4/SDIO_D1_40") (pintype "passive"))
    )
    (net (code "65") (name "unconnected-(U1-PC10{slash}U4_TX{slash}SDIO_D2-Pad51)") (class "Default")
      (node (ref "U1") (pin "51") (pinfunction "PC10/U4_TX/SDIO_D2_51") (pintype "passive"))
    )
    (net (code "66") (name "unconnected-(U1-PC11{slash}U4_RX{slash}SDIO_D3-Pad52)") (class "Default")
      (node (ref "U1") (pin "52") (pinfunction "PC11/U4_RX/SDIO_D3_52") (pintype "passive"))
    )
    (net (code "67") (name "unconnected-(U1-PC12{slash}U5_TX{slash}SDIO_CK-Pad53)") (class "Default")
      (node (ref "U1") (pin "53") (pinfunction "PC12/U5_TX/SDIO_CK_53") (pintype "passive"))
    )
    (net (code "68") (name "unconnected-(U1-PC13{slash}ANT1-Pad2)") (class "Default")
      (node (ref "U1") (pin "2") (pinfunction "PC13/ANT1_2") (pintype "passive"))
    )
    (net (code "69") (name "unconnected-(U1-PC14{slash}OSC32-Pad3)") (class "Default")
      (node (ref "U1") (pin "3") (pinfunction "PC14/OSC32_3") (pintype "passive"))
    )
    (net (code "70") (name "unconnected-(U1-PC15{slash}OSC32-Pad4)") (class "Default")
      (node (ref "U1") (pin "4") (pinfunction "PC15/OSC32_4") (pintype "passive"))
    )
    (net (code "71") (name "unconnected-(U1-PD2{slash}TIM3_ETR{slash}U5_RX{slash}SDIO_CMD-Pad54)") (class "Default")
      (node (ref "U1") (pin "54") (pinfunction "PD2/TIM3_ETR/U5_RX/SDIO_CMD_54") (pintype "passive"))
    )
  )
)
